# TSOC_NEOLED_R1_2.net
KiCad netlist of a schematic drawn in EAGLE
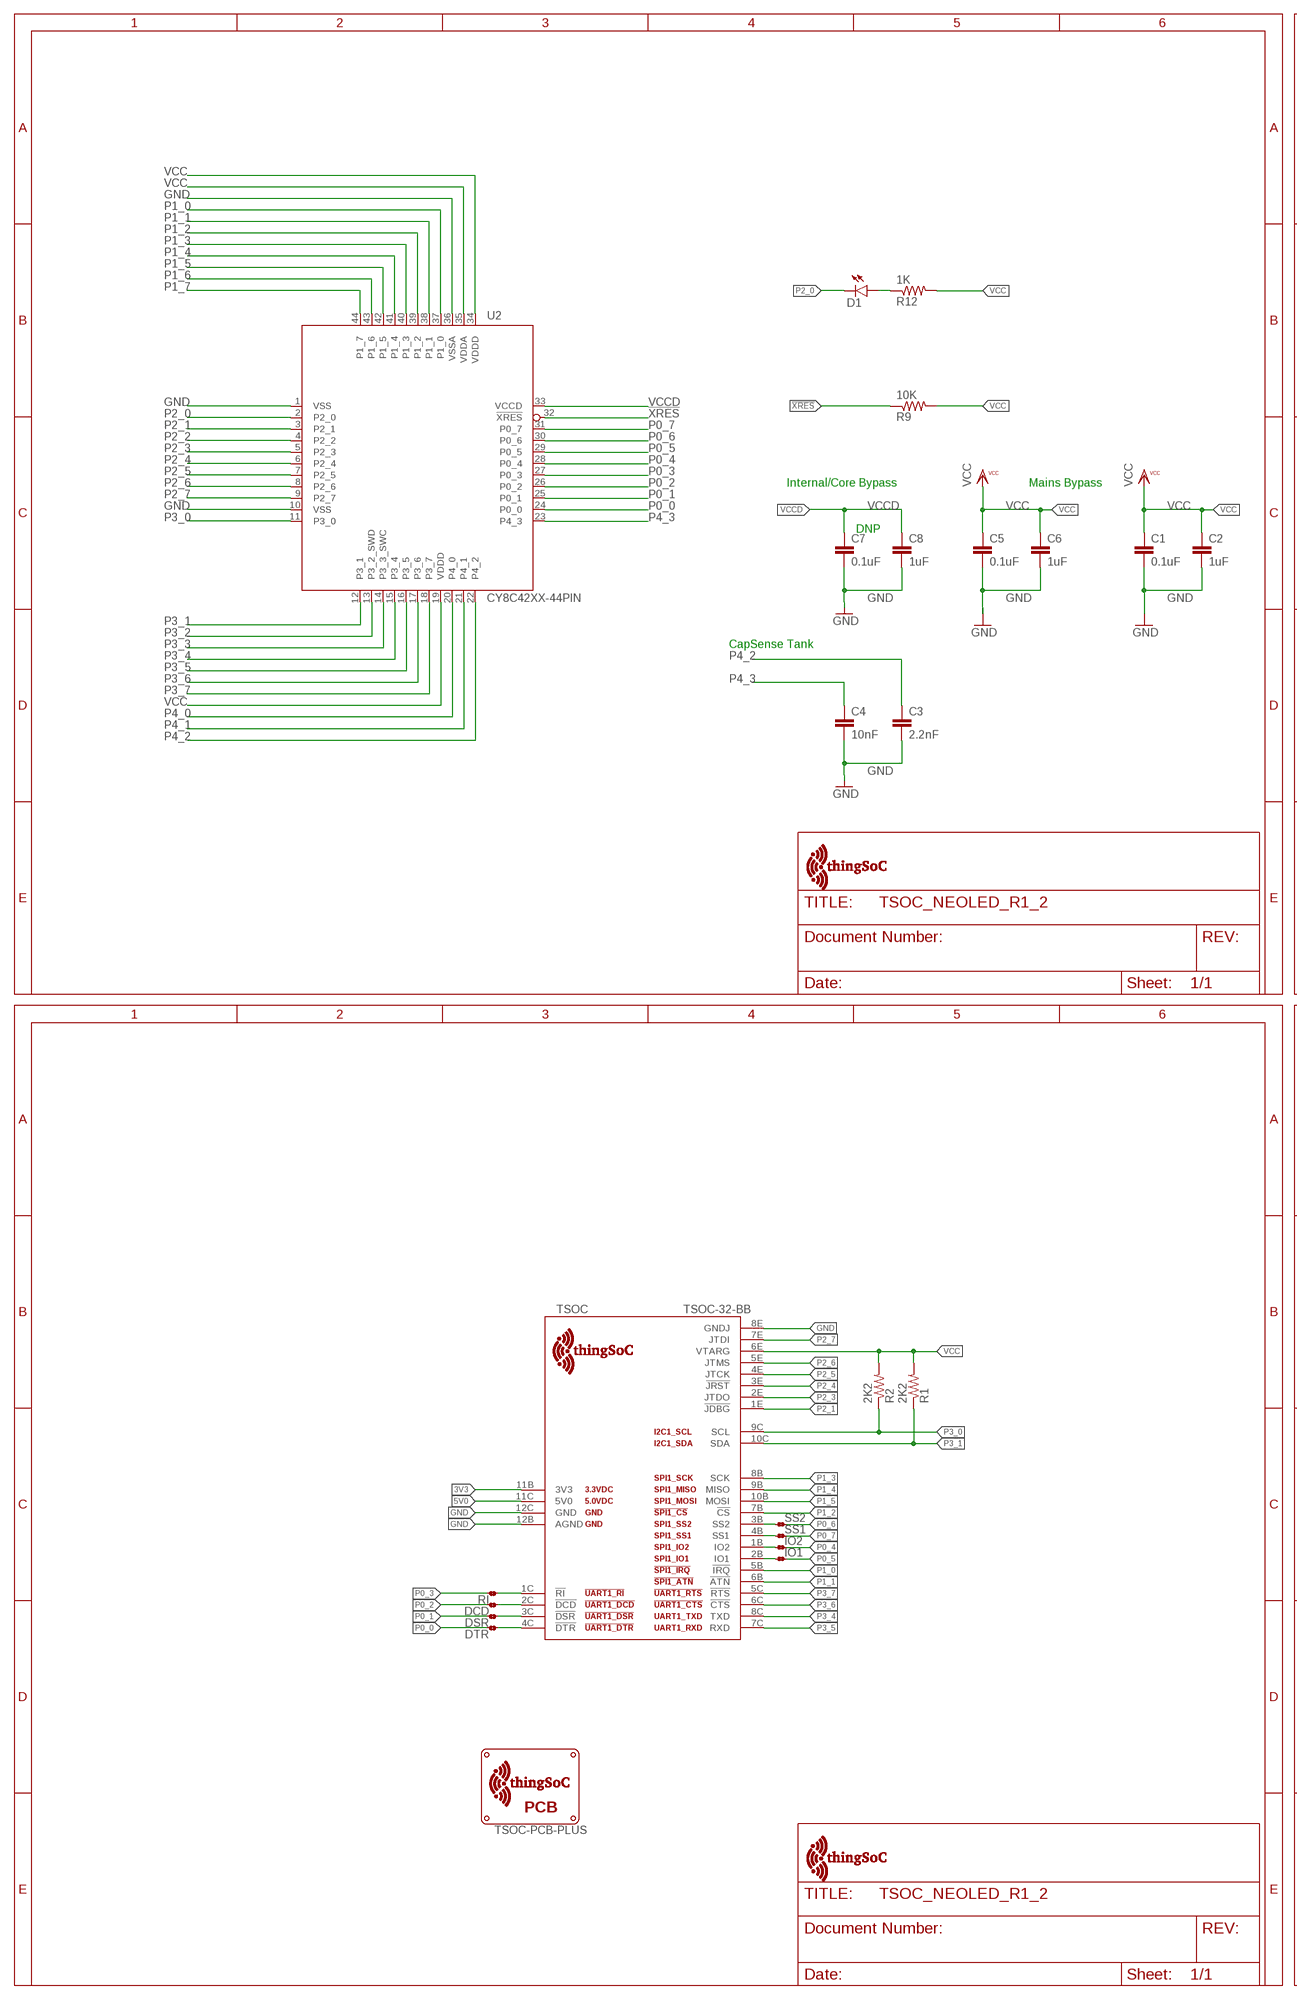
[diagram p0: schematic, sheet 1, part 1 of 2]
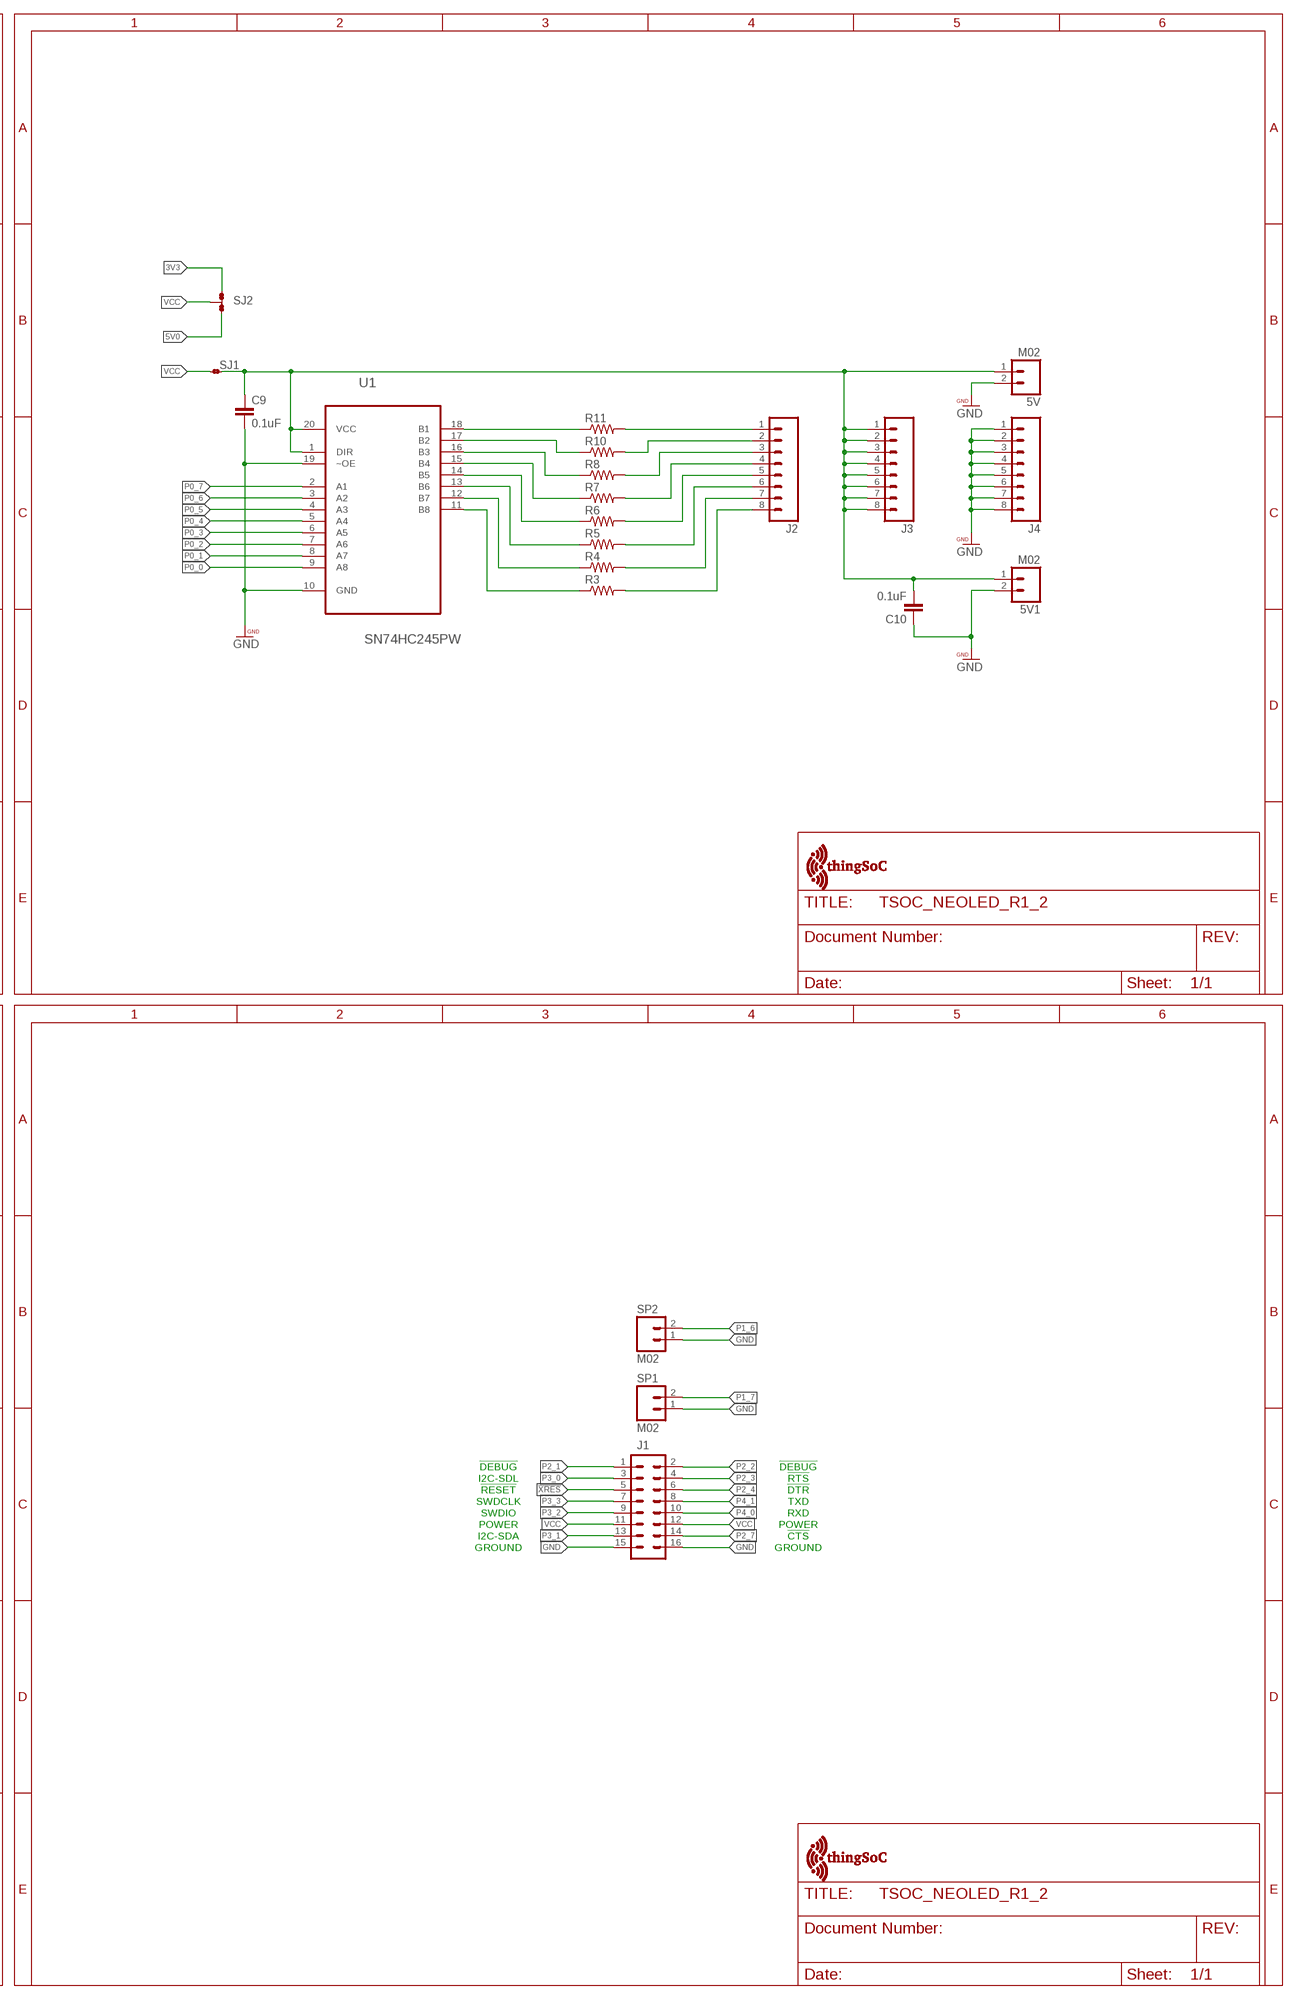
[diagram p1: schematic, sheet 1, part 2 of 2]

(export (version "E")
  (design (tool "Eeschema 10.0.6"))
  (components
    (comp (ref "$$U$1")
      (value "TSOC-LOGO-SMALL")
      (footprint "eagle-import:TSOC-LOGO-SML")
      (libsource (lib "eagle-import") (part "TSOC-LOGO-SMALL"))
    )
    (comp (ref "$$U$2")
      (value "TSOC-LOGO-MED")
      (footprint "eagle-import:TSOC-LOGO-MED")
      (libsource (lib "eagle-import") (part "TSOC-LOGO-MED"))
    )
    (comp (ref "5V")
      (value "M02")
      (footprint "eagle-import:1X02")
      (libsource (lib "eagle-import") (part "M02"))
    )
    (comp (ref "5V1")
      (value "M02")
      (footprint "eagle-import:1X02")
      (libsource (lib "eagle-import") (part "M02"))
    )
    (comp (ref "C1")
      (value "0.1uF")
      (footprint "eagle-import:0603-CAP")
      (libsource (lib "eagle-import") (part "CAP0603-CAP"))
    )
    (comp (ref "C2")
      (value "1uF")
      (footprint "eagle-import:0603-CAP")
      (libsource (lib "eagle-import") (part "CAP0603-CAP"))
    )
    (comp (ref "C3")
      (value "2.2nF")
      (footprint "eagle-import:0603-CAP")
      (libsource (lib "eagle-import") (part "CAP0603-CAP"))
    )
    (comp (ref "C4")
      (value "10nF")
      (footprint "eagle-import:0603-CAP")
      (libsource (lib "eagle-import") (part "CAP0603-CAP"))
    )
    (comp (ref "C5")
      (value "0.1uF")
      (footprint "eagle-import:0603-CAP")
      (libsource (lib "eagle-import") (part "CAP0603-CAP"))
    )
    (comp (ref "C6")
      (value "1uF")
      (footprint "eagle-import:0603-CAP")
      (libsource (lib "eagle-import") (part "CAP0603-CAP"))
    )
    (comp (ref "C7")
      (value "0.1uF")
      (footprint "eagle-import:0603-CAP")
      (libsource (lib "eagle-import") (part "CAP0603-CAP"))
    )
    (comp (ref "C8")
      (value "1uF")
      (footprint "eagle-import:0603-CAP")
      (libsource (lib "eagle-import") (part "CAP0603-CAP"))
    )
    (comp (ref "C9")
      (value "0.1uF")
      (footprint "eagle-import:0603-CAP")
      (libsource (lib "eagle-import") (part "CAP0603-CAP"))
    )
    (comp (ref "C10")
      (value "0.1uF")
      (footprint "eagle-import:0603-CAP")
      (libsource (lib "eagle-import") (part "CAP0603-CAP"))
    )
    (comp (ref "D1")
      (value "LED0603")
      (footprint "eagle-import:LED-0603")
      (libsource (lib "eagle-import") (part "LED0603"))
    )
    (comp (ref "DCD")
      (value "JMP-2-NO")
      (footprint "eagle-import:JMP-2-NO")
      (libsource (lib "eagle-import") (part "JMP-2-NO"))
    )
    (comp (ref "DSR")
      (value "JMP-2-NO")
      (footprint "eagle-import:JMP-2-NO")
      (libsource (lib "eagle-import") (part "JMP-2-NO"))
    )
    (comp (ref "DTR")
      (value "JMP-2-NO")
      (footprint "eagle-import:JMP-2-NO")
      (libsource (lib "eagle-import") (part "JMP-2-NO"))
    )
    (comp (ref "IO1")
      (value "JMP-2-NO")
      (footprint "eagle-import:JMP-2-NO")
      (libsource (lib "eagle-import") (part "JMP-2-NO"))
    )
    (comp (ref "IO2")
      (value "JMP-2-NO")
      (footprint "eagle-import:JMP-2-NO")
      (libsource (lib "eagle-import") (part "JMP-2-NO"))
    )
    (comp (ref "J1")
      (value "M08X2")
      (footprint "eagle-import:2X8")
      (libsource (lib "eagle-import") (part "M08X2"))
    )
    (comp (ref "J2")
      (value "M08")
      (footprint "eagle-import:1X08_ROUND")
      (libsource (lib "eagle-import") (part "M08"))
    )
    (comp (ref "J3")
      (value "M08")
      (footprint "eagle-import:1X08_ROUND")
      (libsource (lib "eagle-import") (part "M08"))
    )
    (comp (ref "J4")
      (value "M08")
      (footprint "eagle-import:1X08_ROUND")
      (libsource (lib "eagle-import") (part "M08"))
    )
    (comp (ref "R1")
      (value "2K2")
      (footprint "eagle-import:0603-RES")
      (libsource (lib "eagle-import") (part "RESISTOR_SFE0603-RES"))
    )
    (comp (ref "R2")
      (value "2K2")
      (footprint "eagle-import:0603-RES")
      (libsource (lib "eagle-import") (part "RESISTOR_SFE0603-RES"))
    )
    (comp (ref "R3")
      (value "RESISTOR0603-RES")
      (footprint "eagle-import:0603-RES")
      (libsource (lib "eagle-import") (part "RESISTOR0603-RES"))
    )
    (comp (ref "R4")
      (value "RESISTOR0603-RES")
      (footprint "eagle-import:0603-RES")
      (libsource (lib "eagle-import") (part "RESISTOR0603-RES"))
    )
    (comp (ref "R5")
      (value "RESISTOR0603-RES")
      (footprint "eagle-import:0603-RES")
      (libsource (lib "eagle-import") (part "RESISTOR0603-RES"))
    )
    (comp (ref "R6")
      (value "RESISTOR0603-RES")
      (footprint "eagle-import:0603-RES")
      (libsource (lib "eagle-import") (part "RESISTOR0603-RES"))
    )
    (comp (ref "R7")
      (value "RESISTOR0603-RES")
      (footprint "eagle-import:0603-RES")
      (libsource (lib "eagle-import") (part "RESISTOR0603-RES"))
    )
    (comp (ref "R8")
      (value "RESISTOR0603-RES")
      (footprint "eagle-import:0603-RES")
      (libsource (lib "eagle-import") (part "RESISTOR0603-RES"))
    )
    (comp (ref "R9")
      (value "10K")
      (footprint "eagle-import:0603-RES")
      (libsource (lib "eagle-import") (part "RESISTOR_SFE0603-RES"))
    )
    (comp (ref "R10")
      (value "RESISTOR0603-RES")
      (footprint "eagle-import:0603-RES")
      (libsource (lib "eagle-import") (part "RESISTOR0603-RES"))
    )
    (comp (ref "R11")
      (value "RESISTOR0603-RES")
      (footprint "eagle-import:0603-RES")
      (libsource (lib "eagle-import") (part "RESISTOR0603-RES"))
    )
    (comp (ref "R12")
      (value "1K")
      (footprint "eagle-import:0603-RES")
      (libsource (lib "eagle-import") (part "RESISTOR_SFE0603-RES"))
    )
    (comp (ref "RI")
      (value "JMP-2-NO")
      (footprint "eagle-import:JMP-2-NO")
      (libsource (lib "eagle-import") (part "JMP-2-NO"))
    )
    (comp (ref "SJ1")
      (value "JMP-2-NC")
      (footprint "eagle-import:JMP-2-NC")
      (libsource (lib "eagle-import") (part "JMP-2-NC"))
    )
    (comp (ref "SJ2")
      (value "JMP-3-NC")
      (footprint "eagle-import:JMP-3-NC")
      (libsource (lib "eagle-import") (part "JMP-3-NC"))
    )
    (comp (ref "SP1")
      (value "M02")
      (footprint "eagle-import:1X02")
      (libsource (lib "eagle-import") (part "M02"))
    )
    (comp (ref "SP2")
      (value "M02")
      (footprint "eagle-import:1X02")
      (libsource (lib "eagle-import") (part "M02"))
    )
    (comp (ref "SS1")
      (value "JMP-2-NO")
      (footprint "eagle-import:JMP-2-NO")
      (libsource (lib "eagle-import") (part "JMP-2-NO"))
    )
    (comp (ref "SS2")
      (value "JMP-2-NO")
      (footprint "eagle-import:JMP-2-NO")
      (libsource (lib "eagle-import") (part "JMP-2-NO"))
    )
    (comp (ref "TSOC")
      (value "TSOC-32-BB")
      (footprint "eagle-import:TSOC-BB-S32")
      (libsource (lib "eagle-import") (part "TSOC-32-BB"))
    )
    (comp (ref "U$1")
      (value "TSOC-PCB-PLUS")
      (footprint "eagle-import:TSOC-BB-BRD-PLUS")
      (libsource (lib "eagle-import") (part "TSOC-PCB-PLUS"))
    )
    (comp (ref "U$100")
      (value "TSOC-LOGO-SMALL")
      (footprint "eagle-import:TSOC-LOGO-SML")
      (libsource (lib "eagle-import") (part "TSOC-LOGO-SMALL"))
    )
    (comp (ref "U$101")
      (value "TSOC-LOGO-LRG")
      (footprint "eagle-import:TSOC-LOGO-LRG")
      (libsource (lib "eagle-import") (part "TSOC-LOGO-LRG"))
    )
    (comp (ref "U1")
      (value "SN74HC245PW")
      (footprint "eagle-import:SOP65P640X120-20N")
      (libsource (lib "eagle-import") (part "SN74HC245PW"))
    )
    (comp (ref "U2")
      (value "CY8C42XX-44PIN")
      (footprint "eagle-import:TQFP-10X10-44")
      (libsource (lib "eagle-import") (part "CY8C42XX-44PIN"))
    )
  )
  (nets
    (net (code "1") (name "/P4_2") (class "Default")
      (node (ref "C3") (pin "1") (pinfunction "1_1") (pintype "passive"))
      (node (ref "U2") (pin "22") (pinfunction "P4_2_22") (pintype "bidirectional"))
    )
    (net (code "2") (name "/P4_3") (class "Default")
      (node (ref "C4") (pin "1") (pinfunction "1_1") (pintype "passive"))
      (node (ref "U2") (pin "23") (pinfunction "P4_3_23") (pintype "bidirectional"))
    )
    (net (code "3") (name "/~{XRES}") (class "Default")
      (node (ref "J1") (pin "5") (pinfunction "5_5") (pintype "passive"))
      (node (ref "R9") (pin "1") (pinfunction "1_1") (pintype "passive"))
      (node (ref "U2") (pin "32") (pinfunction "~{XRES}_32") (pintype "bidirectional"))
    )
    (net (code "4") (name "3V3") (class "Default")
      (node (ref "SJ2") (pin "1") (pinfunction "1_1") (pintype "passive"))
      (node (ref "TSOC") (pin "11B") (pinfunction "3V3_11B") (pintype "bidirectional"))
    )
    (net (code "5") (name "5V0") (class "Default")
      (node (ref "SJ2") (pin "3") (pinfunction "3_3") (pintype "passive"))
      (node (ref "TSOC") (pin "11C") (pinfunction "5V0_11C") (pintype "bidirectional"))
    )
    (net (code "6") (name "GND") (class "Default")
      (node (ref "5V") (pin "2") (pinfunction "2_2") (pintype "passive"))
      (node (ref "5V1") (pin "2") (pinfunction "2_2") (pintype "passive"))
      (node (ref "C1") (pin "2") (pinfunction "2_2") (pintype "passive"))
      (node (ref "C10") (pin "1") (pinfunction "1_1") (pintype "passive"))
      (node (ref "C2") (pin "2") (pinfunction "2_2") (pintype "passive"))
      (node (ref "C3") (pin "2") (pinfunction "2_2") (pintype "passive"))
      (node (ref "C4") (pin "2") (pinfunction "2_2") (pintype "passive"))
      (node (ref "C5") (pin "2") (pinfunction "2_2") (pintype "passive"))
      (node (ref "C6") (pin "2") (pinfunction "2_2") (pintype "passive"))
      (node (ref "C7") (pin "2") (pinfunction "2_2") (pintype "passive"))
      (node (ref "C8") (pin "2") (pinfunction "2_2") (pintype "passive"))
      (node (ref "C9") (pin "2") (pinfunction "2_2") (pintype "passive"))
      (node (ref "J1") (pin "15") (pinfunction "15_15") (pintype "passive"))
      (node (ref "J1") (pin "16") (pinfunction "16_16") (pintype "passive"))
      (node (ref "J4") (pin "1") (pinfunction "1_1") (pintype "passive"))
      (node (ref "J4") (pin "2") (pinfunction "2_2") (pintype "passive"))
      (node (ref "J4") (pin "3") (pinfunction "3_3") (pintype "passive"))
      (node (ref "J4") (pin "4") (pinfunction "4_4") (pintype "passive"))
      (node (ref "J4") (pin "5") (pinfunction "5_5") (pintype "passive"))
      (node (ref "J4") (pin "6") (pinfunction "6_6") (pintype "passive"))
      (node (ref "J4") (pin "7") (pinfunction "7_7") (pintype "passive"))
      (node (ref "J4") (pin "8") (pinfunction "8_8") (pintype "passive"))
      (node (ref "SP1") (pin "1") (pinfunction "1_1") (pintype "passive"))
      (node (ref "SP2") (pin "1") (pinfunction "1_1") (pintype "passive"))
      (node (ref "TSOC") (pin "12B") (pinfunction "AGND_12B") (pintype "bidirectional"))
      (node (ref "TSOC") (pin "12C") (pinfunction "GND_12C") (pintype "bidirectional"))
      (node (ref "TSOC") (pin "8E") (pinfunction "GNDJ_8E") (pintype "bidirectional"))
      (node (ref "U1") (pin "10") (pinfunction "GND_10") (pintype "input"))
      (node (ref "U1") (pin "19") (pinfunction "~{OE}_19") (pintype "input"))
      (node (ref "U2") (pin "1") (pinfunction "VSS_1") (pintype "bidirectional"))
      (node (ref "U2") (pin "10") (pinfunction "VSS_10") (pintype "bidirectional"))
      (node (ref "U2") (pin "36") (pinfunction "VSSA_36") (pintype "bidirectional"))
    )
    (net (code "7") (name "Net-(D1-PadA)") (class "Default")
      (node (ref "D1") (pin "A") (pinfunction "A_A") (pintype "passive"))
      (node (ref "R12") (pin "1") (pinfunction "1_1") (pintype "passive"))
    )
    (net (code "8") (name "Net-(J2-Pad1)") (class "Default")
      (node (ref "J2") (pin "1") (pinfunction "1_1") (pintype "passive"))
      (node (ref "R11") (pin "2") (pinfunction "2_2") (pintype "passive"))
    )
    (net (code "9") (name "Net-(J2-Pad2)") (class "Default")
      (node (ref "J2") (pin "2") (pinfunction "2_2") (pintype "passive"))
      (node (ref "R10") (pin "2") (pinfunction "2_2") (pintype "passive"))
    )
    (net (code "10") (name "Net-(J2-Pad3)") (class "Default")
      (node (ref "J2") (pin "3") (pinfunction "3_3") (pintype "passive"))
      (node (ref "R8") (pin "2") (pinfunction "2_2") (pintype "passive"))
    )
    (net (code "11") (name "Net-(J2-Pad4)") (class "Default")
      (node (ref "J2") (pin "4") (pinfunction "4_4") (pintype "passive"))
      (node (ref "R7") (pin "2") (pinfunction "2_2") (pintype "passive"))
    )
    (net (code "12") (name "Net-(J2-Pad5)") (class "Default")
      (node (ref "J2") (pin "5") (pinfunction "5_5") (pintype "passive"))
      (node (ref "R6") (pin "2") (pinfunction "2_2") (pintype "passive"))
    )
    (net (code "13") (name "Net-(J2-Pad6)") (class "Default")
      (node (ref "J2") (pin "6") (pinfunction "6_6") (pintype "passive"))
      (node (ref "R5") (pin "2") (pinfunction "2_2") (pintype "passive"))
    )
    (net (code "14") (name "Net-(J2-Pad7)") (class "Default")
      (node (ref "J2") (pin "7") (pinfunction "7_7") (pintype "passive"))
      (node (ref "R4") (pin "2") (pinfunction "2_2") (pintype "passive"))
    )
    (net (code "15") (name "Net-(J2-Pad8)") (class "Default")
      (node (ref "J2") (pin "8") (pinfunction "8_8") (pintype "passive"))
      (node (ref "R3") (pin "2") (pinfunction "2_2") (pintype "passive"))
    )
    (net (code "16") (name "Net-(TSOC-IO1)") (class "Default")
      (node (ref "IO1") (pin "1") (pinfunction "1_1") (pintype "passive"))
      (node (ref "TSOC") (pin "2B") (pinfunction "IO1_2B") (pintype "bidirectional"))
    )
    (net (code "17") (name "Net-(TSOC-IO2)") (class "Default")
      (node (ref "IO2") (pin "1") (pinfunction "1_1") (pintype "passive"))
      (node (ref "TSOC") (pin "1B") (pinfunction "IO2_1B") (pintype "bidirectional"))
    )
    (net (code "18") (name "Net-(TSOC-SS1)") (class "Default")
      (node (ref "SS1") (pin "1") (pinfunction "1_1") (pintype "passive"))
      (node (ref "TSOC") (pin "4B") (pinfunction "SS1_4B") (pintype "bidirectional"))
    )
    (net (code "19") (name "Net-(TSOC-SS2)") (class "Default")
      (node (ref "SS2") (pin "1") (pinfunction "1_1") (pintype "passive"))
      (node (ref "TSOC") (pin "3B") (pinfunction "SS2_3B") (pintype "bidirectional"))
    )
    (net (code "20") (name "Net-(TSOC-~{DCD})") (class "Default")
      (node (ref "DCD") (pin "1") (pinfunction "1_1") (pintype "passive"))
      (node (ref "TSOC") (pin "2C") (pinfunction "~{DCD}_2C") (pintype "bidirectional"))
    )
    (net (code "21") (name "Net-(TSOC-~{DSR})") (class "Default")
      (node (ref "DSR") (pin "1") (pinfunction "1_1") (pintype "passive"))
      (node (ref "TSOC") (pin "3C") (pinfunction "~{DSR}_3C") (pintype "bidirectional"))
    )
    (net (code "22") (name "Net-(TSOC-~{DTR})") (class "Default")
      (node (ref "DTR") (pin "1") (pinfunction "1_1") (pintype "passive"))
      (node (ref "TSOC") (pin "4C") (pinfunction "~{DTR}_4C") (pintype "bidirectional"))
    )
    (net (code "23") (name "Net-(TSOC-~{RI})") (class "Default")
      (node (ref "RI") (pin "1") (pinfunction "1_1") (pintype "passive"))
      (node (ref "TSOC") (pin "1C") (pinfunction "~{RI}_1C") (pintype "bidirectional"))
    )
    (net (code "24") (name "Net-(U1-B1)") (class "Default")
      (node (ref "R11") (pin "1") (pinfunction "1_1") (pintype "passive"))
      (node (ref "U1") (pin "18") (pinfunction "B1_18") (pintype "bidirectional"))
    )
    (net (code "25") (name "Net-(U1-B2)") (class "Default")
      (node (ref "R10") (pin "1") (pinfunction "1_1") (pintype "passive"))
      (node (ref "U1") (pin "17") (pinfunction "B2_17") (pintype "bidirectional"))
    )
    (net (code "26") (name "Net-(U1-B3)") (class "Default")
      (node (ref "R8") (pin "1") (pinfunction "1_1") (pintype "passive"))
      (node (ref "U1") (pin "16") (pinfunction "B3_16") (pintype "bidirectional"))
    )
    (net (code "27") (name "Net-(U1-B4)") (class "Default")
      (node (ref "R7") (pin "1") (pinfunction "1_1") (pintype "passive"))
      (node (ref "U1") (pin "15") (pinfunction "B4_15") (pintype "bidirectional"))
    )
    (net (code "28") (name "Net-(U1-B5)") (class "Default")
      (node (ref "R6") (pin "1") (pinfunction "1_1") (pintype "passive"))
      (node (ref "U1") (pin "14") (pinfunction "B5_14") (pintype "bidirectional"))
    )
    (net (code "29") (name "Net-(U1-B6)") (class "Default")
      (node (ref "R5") (pin "1") (pinfunction "1_1") (pintype "passive"))
      (node (ref "U1") (pin "13") (pinfunction "B6_13") (pintype "bidirectional"))
    )
    (net (code "30") (name "Net-(U1-B7)") (class "Default")
      (node (ref "R4") (pin "1") (pinfunction "1_1") (pintype "passive"))
      (node (ref "U1") (pin "12") (pinfunction "B7_12") (pintype "bidirectional"))
    )
    (net (code "31") (name "Net-(U1-B8)") (class "Default")
      (node (ref "R3") (pin "1") (pinfunction "1_1") (pintype "passive"))
      (node (ref "U1") (pin "11") (pinfunction "B8_11") (pintype "bidirectional"))
    )
    (net (code "32") (name "Net-(U1-DIR)") (class "Default")
      (node (ref "5V") (pin "1") (pinfunction "1_1") (pintype "passive"))
      (node (ref "5V1") (pin "1") (pinfunction "1_1") (pintype "passive"))
      (node (ref "C10") (pin "2") (pinfunction "2_2") (pintype "passive"))
      (node (ref "C9") (pin "1") (pinfunction "1_1") (pintype "passive"))
      (node (ref "J3") (pin "1") (pinfunction "1_1") (pintype "passive"))
      (node (ref "J3") (pin "2") (pinfunction "2_2") (pintype "passive"))
      (node (ref "J3") (pin "3") (pinfunction "3_3") (pintype "passive"))
      (node (ref "J3") (pin "4") (pinfunction "4_4") (pintype "passive"))
      (node (ref "J3") (pin "5") (pinfunction "5_5") (pintype "passive"))
      (node (ref "J3") (pin "6") (pinfunction "6_6") (pintype "passive"))
      (node (ref "J3") (pin "7") (pinfunction "7_7") (pintype "passive"))
      (node (ref "J3") (pin "8") (pinfunction "8_8") (pintype "passive"))
      (node (ref "SJ1") (pin "2") (pinfunction "2_2") (pintype "passive"))
      (node (ref "U1") (pin "1") (pinfunction "DIR_1") (pintype "input"))
      (node (ref "U1") (pin "20") (pinfunction "VCC_20") (pintype "power_in"))
    )
    (net (code "33") (name "P0_0") (class "Default")
      (node (ref "DTR") (pin "2") (pinfunction "2_2") (pintype "passive"))
      (node (ref "U1") (pin "9") (pinfunction "A8_9") (pintype "bidirectional"))
      (node (ref "U2") (pin "24") (pinfunction "P0_0_24") (pintype "bidirectional"))
    )
    (net (code "34") (name "P0_1") (class "Default")
      (node (ref "DSR") (pin "2") (pinfunction "2_2") (pintype "passive"))
      (node (ref "U1") (pin "8") (pinfunction "A7_8") (pintype "bidirectional"))
      (node (ref "U2") (pin "25") (pinfunction "P0_1_25") (pintype "bidirectional"))
    )
    (net (code "35") (name "P0_2") (class "Default")
      (node (ref "DCD") (pin "2") (pinfunction "2_2") (pintype "passive"))
      (node (ref "U1") (pin "7") (pinfunction "A6_7") (pintype "bidirectional"))
      (node (ref "U2") (pin "26") (pinfunction "P0_2_26") (pintype "input"))
    )
    (net (code "36") (name "P0_3") (class "Default")
      (node (ref "RI") (pin "2") (pinfunction "2_2") (pintype "passive"))
      (node (ref "U1") (pin "6") (pinfunction "A5_6") (pintype "bidirectional"))
      (node (ref "U2") (pin "27") (pinfunction "P0_3_27") (pintype "bidirectional"))
    )
    (net (code "37") (name "P0_4") (class "Default")
      (node (ref "IO2") (pin "2") (pinfunction "2_2") (pintype "passive"))
      (node (ref "U1") (pin "5") (pinfunction "A4_5") (pintype "bidirectional"))
      (node (ref "U2") (pin "28") (pinfunction "P0_4_28") (pintype "bidirectional"))
    )
    (net (code "38") (name "P0_5") (class "Default")
      (node (ref "IO1") (pin "2") (pinfunction "2_2") (pintype "passive"))
      (node (ref "U1") (pin "4") (pinfunction "A3_4") (pintype "bidirectional"))
      (node (ref "U2") (pin "29") (pinfunction "P0_5_29") (pintype "bidirectional"))
    )
    (net (code "39") (name "P0_6") (class "Default")
      (node (ref "SS2") (pin "2") (pinfunction "2_2") (pintype "passive"))
      (node (ref "U1") (pin "3") (pinfunction "A2_3") (pintype "bidirectional"))
      (node (ref "U2") (pin "30") (pinfunction "P0_6_30") (pintype "power_in"))
    )
    (net (code "40") (name "P0_7") (class "Default")
      (node (ref "SS1") (pin "2") (pinfunction "2_2") (pintype "passive"))
      (node (ref "U1") (pin "2") (pinfunction "A1_2") (pintype "bidirectional"))
      (node (ref "U2") (pin "31") (pinfunction "P0_7_31") (pintype "bidirectional"))
    )
    (net (code "41") (name "P1_0") (class "Default")
      (node (ref "TSOC") (pin "5B") (pinfunction "~{IRQ}_5B") (pintype "bidirectional"))
      (node (ref "U2") (pin "37") (pinfunction "P1_0_37") (pintype "bidirectional"))
    )
    (net (code "42") (name "P1_1") (class "Default")
      (node (ref "TSOC") (pin "6B") (pinfunction "~{ATN}_6B") (pintype "bidirectional"))
      (node (ref "U2") (pin "38") (pinfunction "P1_1_38") (pintype "bidirectional"))
    )
    (net (code "43") (name "P1_2") (class "Default")
      (node (ref "TSOC") (pin "7B") (pinfunction "~{CS}_7B") (pintype "bidirectional"))
      (node (ref "U2") (pin "39") (pinfunction "P1_2_39") (pintype "power_in"))
    )
    (net (code "44") (name "P1_3") (class "Default")
      (node (ref "TSOC") (pin "8B") (pinfunction "SCK_8B") (pintype "bidirectional"))
      (node (ref "U2") (pin "40") (pinfunction "P1_3_40") (pintype "bidirectional"))
    )
    (net (code "45") (name "P1_4") (class "Default")
      (node (ref "TSOC") (pin "9B") (pinfunction "MISO_9B") (pintype "bidirectional"))
      (node (ref "U2") (pin "41") (pinfunction "P1_4_41") (pintype "bidirectional"))
    )
    (net (code "46") (name "P1_5") (class "Default")
      (node (ref "TSOC") (pin "10B") (pinfunction "MOSI_10B") (pintype "bidirectional"))
      (node (ref "U2") (pin "42") (pinfunction "P1_5_42") (pintype "bidirectional"))
    )
    (net (code "47") (name "P1_6") (class "Default")
      (node (ref "SP2") (pin "2") (pinfunction "2_2") (pintype "passive"))
      (node (ref "U2") (pin "43") (pinfunction "P1_6_43") (pintype "bidirectional"))
    )
    (net (code "48") (name "P1_7") (class "Default")
      (node (ref "SP1") (pin "2") (pinfunction "2_2") (pintype "passive"))
      (node (ref "U2") (pin "44") (pinfunction "P1_7_44") (pintype "bidirectional"))
    )
    (net (code "49") (name "P2_0") (class "Default")
      (node (ref "D1") (pin "C") (pinfunction "C_C") (pintype "passive"))
      (node (ref "U2") (pin "2") (pinfunction "P2_0_2") (pintype "bidirectional"))
    )
    (net (code "50") (name "P2_1") (class "Default")
      (node (ref "J1") (pin "1") (pinfunction "1_1") (pintype "passive"))
      (node (ref "TSOC") (pin "1E") (pinfunction "~{JDBG}_1E") (pintype "bidirectional"))
      (node (ref "U2") (pin "3") (pinfunction "P2_1_3") (pintype "bidirectional"))
    )
    (net (code "51") (name "P2_2") (class "Default")
      (node (ref "J1") (pin "2") (pinfunction "2_2") (pintype "passive"))
      (node (ref "U2") (pin "4") (pinfunction "P2_2_4") (pintype "power_in"))
    )
    (net (code "52") (name "P2_3") (class "Default")
      (node (ref "J1") (pin "4") (pinfunction "4_4") (pintype "passive"))
      (node (ref "TSOC") (pin "2E") (pinfunction "JTDO_2E") (pintype "bidirectional"))
      (node (ref "U2") (pin "5") (pinfunction "P2_3_5") (pintype "bidirectional"))
    )
    (net (code "53") (name "P2_4") (class "Default")
      (node (ref "J1") (pin "6") (pinfunction "6_6") (pintype "passive"))
      (node (ref "TSOC") (pin "3E") (pinfunction "~{JRST}_3E") (pintype "bidirectional"))
      (node (ref "U2") (pin "6") (pinfunction "P2_4_6") (pintype "bidirectional"))
    )
    (net (code "54") (name "P2_5") (class "Default")
      (node (ref "TSOC") (pin "4E") (pinfunction "JTCK_4E") (pintype "bidirectional"))
      (node (ref "U2") (pin "7") (pinfunction "P2_5_7") (pintype "bidirectional"))
    )
    (net (code "55") (name "P2_6") (class "Default")
      (node (ref "TSOC") (pin "5E") (pinfunction "JTMS_5E") (pintype "bidirectional"))
      (node (ref "U2") (pin "8") (pinfunction "P2_6_8") (pintype "power_in"))
    )
    (net (code "56") (name "P2_7") (class "Default")
      (node (ref "J1") (pin "14") (pinfunction "14_14") (pintype "passive"))
      (node (ref "TSOC") (pin "7E") (pinfunction "JTDI_7E") (pintype "bidirectional"))
      (node (ref "U2") (pin "9") (pinfunction "P2_7_9") (pintype "bidirectional"))
    )
    (net (code "57") (name "P3_0") (class "Default")
      (node (ref "J1") (pin "3") (pinfunction "3_3") (pintype "passive"))
      (node (ref "R2") (pin "1") (pinfunction "1_1") (pintype "passive"))
      (node (ref "TSOC") (pin "9C") (pinfunction "SCL_9C") (pintype "bidirectional"))
      (node (ref "U2") (pin "11") (pinfunction "P3_0_11") (pintype "bidirectional"))
    )
    (net (code "58") (name "P3_1") (class "Default")
      (node (ref "J1") (pin "13") (pinfunction "13_13") (pintype "passive"))
      (node (ref "R1") (pin "1") (pinfunction "1_1") (pintype "passive"))
      (node (ref "TSOC") (pin "10C") (pinfunction "SDA_10C") (pintype "bidirectional"))
      (node (ref "U2") (pin "12") (pinfunction "P3_1_12") (pintype "bidirectional"))
    )
    (net (code "59") (name "P3_2") (class "Default")
      (node (ref "J1") (pin "9") (pinfunction "9_9") (pintype "passive"))
      (node (ref "U2") (pin "13") (pinfunction "P3_2_SWD_13") (pintype "bidirectional"))
    )
    (net (code "60") (name "P3_3") (class "Default")
      (node (ref "J1") (pin "7") (pinfunction "7_7") (pintype "passive"))
      (node (ref "U2") (pin "14") (pinfunction "P3_3_SWC_14") (pintype "bidirectional"))
    )
    (net (code "61") (name "P3_4") (class "Default")
      (node (ref "TSOC") (pin "8C") (pinfunction "TXD_8C") (pintype "bidirectional"))
      (node (ref "U2") (pin "15") (pinfunction "P3_4_15") (pintype "bidirectional"))
    )
    (net (code "62") (name "P3_5") (class "Default")
      (node (ref "TSOC") (pin "7C") (pinfunction "RXD_7C") (pintype "bidirectional"))
      (node (ref "U2") (pin "16") (pinfunction "P3_5_16") (pintype "bidirectional"))
    )
    (net (code "63") (name "P3_6") (class "Default")
      (node (ref "TSOC") (pin "6C") (pinfunction "~{CTS}_6C") (pintype "bidirectional"))
      (node (ref "U2") (pin "17") (pinfunction "P3_6_17") (pintype "power_in"))
    )
    (net (code "64") (name "P3_7") (class "Default")
      (node (ref "TSOC") (pin "5C") (pinfunction "~{RTS}_5C") (pintype "bidirectional"))
      (node (ref "U2") (pin "18") (pinfunction "P3_7_18") (pintype "bidirectional"))
    )
    (net (code "65") (name "P4_0") (class "Default")
      (node (ref "J1") (pin "10") (pinfunction "10_10") (pintype "passive"))
      (node (ref "U2") (pin "20") (pinfunction "P4_0_20") (pintype "bidirectional"))
    )
    (net (code "66") (name "P4_1") (class "Default")
      (node (ref "J1") (pin "8") (pinfunction "8_8") (pintype "passive"))
      (node (ref "U2") (pin "21") (pinfunction "P4_1_21") (pintype "bidirectional"))
    )
    (net (code "67") (name "VCC") (class "Default")
      (node (ref "C1") (pin "1") (pinfunction "1_1") (pintype "passive"))
      (node (ref "C2") (pin "1") (pinfunction "1_1") (pintype "passive"))
      (node (ref "C5") (pin "1") (pinfunction "1_1") (pintype "passive"))
      (node (ref "C6") (pin "1") (pinfunction "1_1") (pintype "passive"))
      (node (ref "J1") (pin "11") (pinfunction "11_11") (pintype "passive"))
      (node (ref "J1") (pin "12") (pinfunction "12_12") (pintype "passive"))
      (node (ref "R1") (pin "2") (pinfunction "2_2") (pintype "passive"))
      (node (ref "R12") (pin "2") (pinfunction "2_2") (pintype "passive"))
      (node (ref "R2") (pin "2") (pinfunction "2_2") (pintype "passive"))
      (node (ref "R9") (pin "2") (pinfunction "2_2") (pintype "passive"))
      (node (ref "SJ1") (pin "1") (pinfunction "1_1") (pintype "passive"))
      (node (ref "SJ2") (pin "2") (pinfunction "2_2") (pintype "passive"))
      (node (ref "TSOC") (pin "6E") (pinfunction "VTARG_6E") (pintype "bidirectional"))
      (node (ref "U2") (pin "19") (pinfunction "VDDD_19") (pintype "bidirectional"))
      (node (ref "U2") (pin "34") (pinfunction "VDDD_34") (pintype "bidirectional"))
      (node (ref "U2") (pin "35") (pinfunction "VDDA_35") (pintype "bidirectional"))
    )
    (net (code "68") (name "VCCD") (class "Default")
      (node (ref "C7") (pin "1") (pinfunction "1_1") (pintype "passive"))
      (node (ref "C8") (pin "1") (pinfunction "1_1") (pintype "passive"))
      (node (ref "U2") (pin "33") (pinfunction "VCCD_33") (pintype "bidirectional"))
    )
  )
)
